# MAX77857.net
KiCad netlist of a schematic drawn in Altium Designer
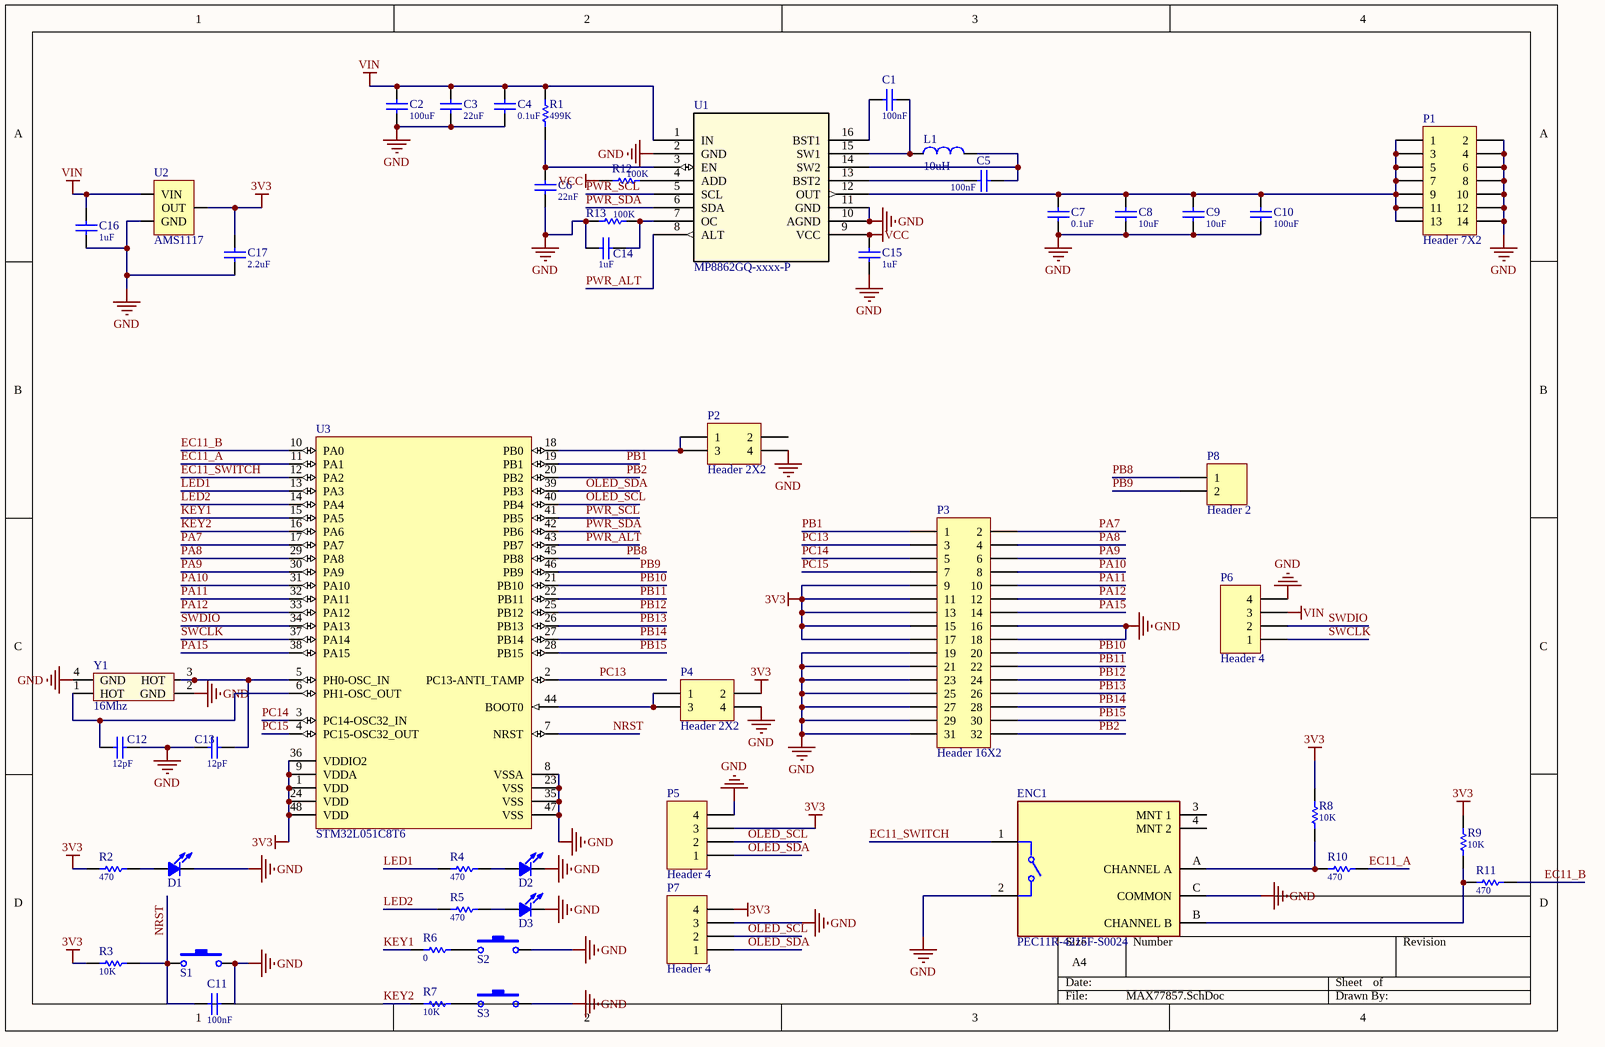
[diagram p0: MAX77857.SchDoc]

(export (version "E")
  (design (tool "Eeschema 10.0.6"))
  (components
    (comp (ref "C1")
      (value "100nF")
      (footprint "C0603-L")
      (description "贴片瓷片电容")
      (fields (field (name "Comment") "Cap-S"))
      (libsource (lib "CommonUsed") (part "Cap-S"))
    )
    (comp (ref "C2")
      (value "100uF")
      (footprint "C1206-L")
      (description "贴片瓷片电容")
      (fields (field (name "Comment") "Cap-S"))
      (libsource (lib "CommonUsed") (part "Cap-S"))
    )
    (comp (ref "C3")
      (value "22uF")
      (footprint "C0603-L")
      (description "贴片瓷片电容")
      (fields (field (name "Comment") "Cap-S"))
      (libsource (lib "CommonUsed") (part "Cap-S"))
    )
    (comp (ref "C4")
      (value "0.1uF")
      (footprint "C0603-L")
      (description "贴片瓷片电容")
      (fields (field (name "Comment") "Cap-S"))
      (libsource (lib "CommonUsed") (part "Cap-S"))
    )
    (comp (ref "C5")
      (value "100nF")
      (footprint "C0603-L")
      (description "贴片瓷片电容")
      (fields (field (name "Comment") "Cap-S"))
      (libsource (lib "CommonUsed") (part "Cap-S"))
    )
    (comp (ref "C6")
      (value "22nF")
      (footprint "C0603-L")
      (description "贴片瓷片电容")
      (fields (field (name "Comment") "Cap-S"))
      (libsource (lib "CommonUsed") (part "Cap-S"))
    )
    (comp (ref "C7")
      (value "0.1uF")
      (footprint "C0603-L")
      (description "贴片瓷片电容")
      (fields (field (name "Comment") "Cap-S"))
      (libsource (lib "CommonUsed") (part "Cap-S"))
    )
    (comp (ref "C8")
      (value "10uF")
      (footprint "C1206-L")
      (description "贴片瓷片电容")
      (fields (field (name "Comment") "Cap-S"))
      (libsource (lib "CommonUsed") (part "Cap-S"))
    )
    (comp (ref "C9")
      (value "10uF")
      (footprint "C1206-L")
      (description "贴片瓷片电容")
      (fields (field (name "Comment") "Cap-S"))
      (libsource (lib "CommonUsed") (part "Cap-S"))
    )
    (comp (ref "C10")
      (value "100uF")
      (footprint "C1206-L")
      (description "贴片瓷片电容")
      (fields (field (name "Comment") "Cap-S"))
      (libsource (lib "CommonUsed") (part "Cap-S"))
    )
    (comp (ref "C11")
      (value "100nF")
      (footprint "C0603-L")
      (description "贴片瓷片电容")
      (fields (field (name "Comment") "Cap-S"))
      (libsource (lib "CommonUsed") (part "Cap-S"))
    )
    (comp (ref "C12")
      (value "12pF")
      (footprint "C0603-L")
      (description "贴片瓷片电容")
      (fields (field (name "Comment") "Cap-S"))
      (libsource (lib "CommonUsed") (part "Cap-S"))
    )
    (comp (ref "C13")
      (value "12pF")
      (footprint "C0603-L")
      (description "贴片瓷片电容")
      (fields (field (name "Comment") "Cap-S"))
      (libsource (lib "CommonUsed") (part "Cap-S"))
    )
    (comp (ref "C14")
      (value "1uF")
      (footprint "C0603-L")
      (description "贴片瓷片电容")
      (fields (field (name "Comment") "Cap-S"))
      (libsource (lib "CommonUsed") (part "Cap-S"))
    )
    (comp (ref "C15")
      (value "1uF")
      (footprint "C0603-L")
      (description "贴片瓷片电容")
      (fields (field (name "Comment") "Cap-S"))
      (libsource (lib "CommonUsed") (part "Cap-S"))
    )
    (comp (ref "C16")
      (value "1uF")
      (footprint "C1206-L")
      (description "贴片瓷片电容")
      (fields (field (name "Comment") "Cap-S"))
      (libsource (lib "CommonUsed") (part "Cap-S"))
    )
    (comp (ref "C17")
      (value "2.2uF")
      (footprint "C0603-L")
      (description "贴片瓷片电容")
      (fields (field (name "Comment") "Cap-S"))
      (libsource (lib "CommonUsed") (part "Cap-S"))
    )
    (comp (ref "D1")
      (value "LED")
      (footprint "Led-0805_L")
      (description "发光二极管")
      (libsource (lib "CommonUsed") (part "LED"))
    )
    (comp (ref "D2")
      (value "LED")
      (footprint "Led-0805_L")
      (description "发光二极管")
      (libsource (lib "CommonUsed") (part "LED"))
    )
    (comp (ref "D3")
      (value "LED")
      (footprint "Led-0805_L")
      (description "发光二极管")
      (libsource (lib "CommonUsed") (part "LED"))
    )
    (comp (ref "ENC1")
      (value "PEC11R-4215F-S0024")
      (footprint "FP-PEC11R-4215F-S0024-MFG")
      (description "ROTARY ENCODER MECHANICAL 24PPR")
      (libsource (lib "Altium Content Vault") (part "5f1dd25a4c49fa66e7eeb899730fe11"))
    )
    (comp (ref "L1") (value "10uH") (footprint "L-6.5mm") (libsource (lib "CommonUsed") (part "Inductor")))
    (comp (ref "P1")
      (value "Header 7X2")
      (footprint "HDR2X7")
      (description "Header, 7-Pin, Dual row")
      (fields (field (name "PUBLISHER") "Altium Limited"))
      (libsource (lib "Miscellaneous Connectors") (part "Header 7X2"))
    )
    (comp (ref "P2")
      (value "Header 2X2")
      (footprint "HDR2X2")
      (description "Header, 2-Pin, Dual row")
      (fields (field (name "PUBLISHER") "Altium Limited"))
      (libsource (lib "Miscellaneous Connectors") (part "Header 2X2"))
    )
    (comp (ref "P3")
      (value "Header 16X2")
      (footprint "HDR2X16")
      (description "Header, 16-Pin, Dual row")
      (fields (field (name "PUBLISHER") "Altium Limited"))
      (libsource (lib "Miscellaneous Connectors") (part "Header 16X2"))
    )
    (comp (ref "P4")
      (value "Header 2X2")
      (footprint "HDR2X2")
      (description "Header, 2-Pin, Dual row")
      (fields (field (name "PUBLISHER") "Altium Limited"))
      (libsource (lib "Miscellaneous Connectors") (part "Header 2X2"))
    )
    (comp (ref "P5")
      (value "Header 4")
      (footprint "HDR1X4")
      (description "Header, 4-Pin")
      (fields (field (name "PUBLISHER") "Altium Limited"))
      (libsource (lib "Miscellaneous Connectors") (part "Header 4"))
    )
    (comp (ref "P6")
      (value "Header 4")
      (footprint "HDR1X4")
      (description "Header, 4-Pin")
      (fields (field (name "PUBLISHER") "Altium Limited"))
      (libsource (lib "Miscellaneous Connectors") (part "Header 4"))
    )
    (comp (ref "P7")
      (value "Header 4")
      (footprint "HDR1X4")
      (description "Header, 4-Pin")
      (fields (field (name "PUBLISHER") "Altium Limited"))
      (libsource (lib "Miscellaneous Connectors") (part "Header 4"))
    )
    (comp (ref "P8")
      (value "Header 2")
      (footprint "HDR1X2")
      (description "Header, 2-Pin")
      (fields (field (name "PUBLISHER") "Altium Limited"))
      (libsource (lib "Miscellaneous Connectors") (part "Header 2"))
    )
    (comp (ref "R1")
      (value "499K")
      (footprint "R0603-L")
      (description "贴片电阻")
      (fields (field (name "Comment") "R"))
      (libsource (lib "CommonUsed") (part "Res"))
    )
    (comp (ref "R2")
      (value "470")
      (footprint "R0603-L")
      (description "贴片电阻")
      (fields (field (name "Comment") "R"))
      (libsource (lib "CommonUsed") (part "Res"))
    )
    (comp (ref "R3")
      (value "10K")
      (footprint "R0603-L")
      (description "贴片电阻")
      (fields (field (name "Comment") "R"))
      (libsource (lib "CommonUsed") (part "Res"))
    )
    (comp (ref "R4")
      (value "470")
      (footprint "R0603-L")
      (description "贴片电阻")
      (fields (field (name "Comment") "R"))
      (libsource (lib "CommonUsed") (part "Res"))
    )
    (comp (ref "R5")
      (value "470")
      (footprint "R0603-L")
      (description "贴片电阻")
      (fields (field (name "Comment") "R"))
      (libsource (lib "CommonUsed") (part "Res"))
    )
    (comp (ref "R6")
      (value "0")
      (footprint "R0603-L")
      (description "贴片电阻")
      (fields (field (name "Comment") "R"))
      (libsource (lib "CommonUsed") (part "Res"))
    )
    (comp (ref "R7")
      (value "10K")
      (footprint "R0603-L")
      (description "贴片电阻")
      (fields (field (name "Comment") "R"))
      (libsource (lib "CommonUsed") (part "Res"))
    )
    (comp (ref "R8")
      (value "10K")
      (footprint "R0603-L")
      (description "贴片电阻")
      (fields (field (name "Comment") "R"))
      (libsource (lib "CommonUsed") (part "Res"))
    )
    (comp (ref "R9")
      (value "10K")
      (footprint "R0603-L")
      (description "贴片电阻")
      (fields (field (name "Comment") "R"))
      (libsource (lib "CommonUsed") (part "Res"))
    )
    (comp (ref "R10")
      (value "470")
      (footprint "R0603-L")
      (description "贴片电阻")
      (fields (field (name "Comment") "R"))
      (libsource (lib "CommonUsed") (part "Res"))
    )
    (comp (ref "R11")
      (value "470")
      (footprint "R0603-L")
      (description "贴片电阻")
      (fields (field (name "Comment") "R"))
      (libsource (lib "CommonUsed") (part "Res"))
    )
    (comp (ref "R12")
      (value "100K")
      (footprint "R0603-L")
      (description "贴片电阻")
      (fields (field (name "Comment") "R"))
      (libsource (lib "CommonUsed") (part "Res"))
    )
    (comp (ref "R13")
      (value "100K")
      (footprint "R0603-L")
      (description "贴片电阻")
      (fields (field (name "Comment") "R"))
      (libsource (lib "CommonUsed") (part "Res"))
    )
    (comp (ref "S1")
      (value "SW-PB2")
      (footprint "SW-PB2-SMD")
      (description "贴片式2脚微动开关")
      (libsource (lib "CommonUsed") (part "SW-PB2"))
    )
    (comp (ref "S2")
      (value "SW-PB2")
      (footprint "SW-PB2-SMD")
      (description "贴片式2脚微动开关")
      (libsource (lib "CommonUsed") (part "SW-PB2"))
    )
    (comp (ref "S3")
      (value "SW-PB2")
      (footprint "SW-PB2-SMD")
      (description "贴片式2脚微动开关")
      (libsource (lib "CommonUsed") (part "SW-PB2"))
    )
    (comp (ref "U1")
      (value "MP8862GQ-xxxx-P")
      (footprint "QFN-3x3_MP8862_MNP")
      (description "No Description Available")
      (libsource (lib "MP8862GQ-xxxx-P") (part "MP8862GQ-xxxx-P"))
    )
    (comp (ref "U2") (value "AMS1117") (footprint "SOT-223") (libsource (lib "CommonUsed") (part "AMS1117")))
    (comp (ref "U3")
      (value "STM32L051C8T6")
      (footprint "STM-LQFP48_L")
      (libsource (lib "Altium Content Vault") (part "STM-STM32L051-LQFP-48"))
    )
    (comp (ref "Y1")
      (value "16Mhz")
      (footprint "XTAL3225")
      (description "3225贴片无源晶振")
      (libsource (lib "STM32H743核心板封装库") (part "XTAL_3225"))
    )
  )
  (nets
    (net (code "1") (name "/EC11_A") (class "Default")
      (node (ref "R10") (pin "2") (pinfunction "2_2") (pintype "passive"))
      (node (ref "U3") (pin "11") (pinfunction "PA1_11") (pintype "bidirectional"))
    )
    (net (code "2") (name "/EC11_B") (class "Default")
      (node (ref "R11") (pin "2") (pinfunction "2_2") (pintype "passive"))
      (node (ref "U3") (pin "10") (pinfunction "PA0_10") (pintype "bidirectional"))
    )
    (net (code "3") (name "/EC11_SWITCH") (class "Default")
      (node (ref "ENC1") (pin "1") (pinfunction "1_1") (pintype "passive"))
      (node (ref "U3") (pin "12") (pinfunction "PA2_12") (pintype "bidirectional"))
    )
    (net (code "4") (name "/KEY1") (class "Default")
      (node (ref "R6") (pin "2") (pinfunction "2_2") (pintype "passive"))
      (node (ref "U3") (pin "15") (pinfunction "PA5_15") (pintype "bidirectional"))
    )
    (net (code "5") (name "/KEY2") (class "Default")
      (node (ref "R7") (pin "2") (pinfunction "2_2") (pintype "passive"))
      (node (ref "U3") (pin "16") (pinfunction "PA6_16") (pintype "bidirectional"))
    )
    (net (code "6") (name "/LED1") (class "Default")
      (node (ref "R4") (pin "2") (pinfunction "2_2") (pintype "passive"))
      (node (ref "U3") (pin "13") (pinfunction "PA3_13") (pintype "bidirectional"))
    )
    (net (code "7") (name "/LED2") (class "Default")
      (node (ref "R5") (pin "2") (pinfunction "2_2") (pintype "passive"))
      (node (ref "U3") (pin "14") (pinfunction "PA4_14") (pintype "bidirectional"))
    )
    (net (code "8") (name "/NRST") (class "Default")
      (node (ref "C11") (pin "1") (pinfunction "1_1") (pintype "passive"))
      (node (ref "R3") (pin "1") (pinfunction "1_1") (pintype "passive"))
      (node (ref "S1") (pin "1") (pinfunction "1_1") (pintype "passive"))
      (node (ref "U3") (pin "7") (pinfunction "NRST_7") (pintype "bidirectional"))
    )
    (net (code "9") (name "/OLED_SCL") (class "Default")
      (node (ref "P5") (pin "2") (pinfunction "2_2") (pintype "passive"))
      (node (ref "P7") (pin "2") (pinfunction "2_2") (pintype "passive"))
      (node (ref "U3") (pin "40") (pinfunction "PB4_40") (pintype "bidirectional"))
    )
    (net (code "10") (name "/OLED_SDA") (class "Default")
      (node (ref "P5") (pin "1") (pinfunction "1_1") (pintype "passive"))
      (node (ref "P7") (pin "1") (pinfunction "1_1") (pintype "passive"))
      (node (ref "U3") (pin "39") (pinfunction "PB3_39") (pintype "bidirectional"))
    )
    (net (code "11") (name "/PA7") (class "Default")
      (node (ref "P3") (pin "2") (pinfunction "2_2") (pintype "passive"))
      (node (ref "U3") (pin "17") (pinfunction "PA7_17") (pintype "bidirectional"))
    )
    (net (code "12") (name "/PA8") (class "Default")
      (node (ref "P3") (pin "4") (pinfunction "4_4") (pintype "passive"))
      (node (ref "U3") (pin "29") (pinfunction "PA8_29") (pintype "bidirectional"))
    )
    (net (code "13") (name "/PA9") (class "Default")
      (node (ref "P3") (pin "6") (pinfunction "6_6") (pintype "passive"))
      (node (ref "U3") (pin "30") (pinfunction "PA9_30") (pintype "bidirectional"))
    )
    (net (code "14") (name "/PA10") (class "Default")
      (node (ref "P3") (pin "8") (pinfunction "8_8") (pintype "passive"))
      (node (ref "U3") (pin "31") (pinfunction "PA10_31") (pintype "bidirectional"))
    )
    (net (code "15") (name "/PA11") (class "Default")
      (node (ref "P3") (pin "10") (pinfunction "10_10") (pintype "passive"))
      (node (ref "U3") (pin "32") (pinfunction "PA11_32") (pintype "bidirectional"))
    )
    (net (code "16") (name "/PA12") (class "Default")
      (node (ref "P3") (pin "12") (pinfunction "12_12") (pintype "passive"))
      (node (ref "U3") (pin "33") (pinfunction "PA12_33") (pintype "bidirectional"))
    )
    (net (code "17") (name "/PA15") (class "Default")
      (node (ref "P3") (pin "14") (pinfunction "14_14") (pintype "passive"))
      (node (ref "U3") (pin "38") (pinfunction "PA15_38") (pintype "bidirectional"))
    )
    (net (code "18") (name "/PB1") (class "Default")
      (node (ref "P3") (pin "1") (pinfunction "1_1") (pintype "passive"))
      (node (ref "U3") (pin "19") (pinfunction "PB1_19") (pintype "bidirectional"))
    )
    (net (code "19") (name "/PB2") (class "Default")
      (node (ref "P3") (pin "32") (pinfunction "32_32") (pintype "passive"))
      (node (ref "U3") (pin "20") (pinfunction "PB2_20") (pintype "bidirectional"))
    )
    (net (code "20") (name "/PB8") (class "Default")
      (node (ref "P8") (pin "1") (pinfunction "1_1") (pintype "passive"))
      (node (ref "U3") (pin "45") (pinfunction "PB8_45") (pintype "bidirectional"))
    )
    (net (code "21") (name "/PB9") (class "Default")
      (node (ref "P8") (pin "2") (pinfunction "2_2") (pintype "passive"))
      (node (ref "U3") (pin "46") (pinfunction "PB9_46") (pintype "bidirectional"))
    )
    (net (code "22") (name "/PB10") (class "Default")
      (node (ref "P3") (pin "20") (pinfunction "20_20") (pintype "passive"))
      (node (ref "U3") (pin "21") (pinfunction "PB10_21") (pintype "bidirectional"))
    )
    (net (code "23") (name "/PB11") (class "Default")
      (node (ref "P3") (pin "22") (pinfunction "22_22") (pintype "passive"))
      (node (ref "U3") (pin "22") (pinfunction "PB11_22") (pintype "bidirectional"))
    )
    (net (code "24") (name "/PB12") (class "Default")
      (node (ref "P3") (pin "24") (pinfunction "24_24") (pintype "passive"))
      (node (ref "U3") (pin "25") (pinfunction "PB12_25") (pintype "bidirectional"))
    )
    (net (code "25") (name "/PB13") (class "Default")
      (node (ref "P3") (pin "26") (pinfunction "26_26") (pintype "passive"))
      (node (ref "U3") (pin "26") (pinfunction "PB13_26") (pintype "bidirectional"))
    )
    (net (code "26") (name "/PB14") (class "Default")
      (node (ref "P3") (pin "28") (pinfunction "28_28") (pintype "passive"))
      (node (ref "U3") (pin "27") (pinfunction "PB14_27") (pintype "bidirectional"))
    )
    (net (code "27") (name "/PB15") (class "Default")
      (node (ref "P3") (pin "30") (pinfunction "30_30") (pintype "passive"))
      (node (ref "U3") (pin "28") (pinfunction "PB15_28") (pintype "bidirectional"))
    )
    (net (code "28") (name "/PC13") (class "Default")
      (node (ref "P3") (pin "3") (pinfunction "3_3") (pintype "passive"))
      (node (ref "U3") (pin "2") (pinfunction "PC13-ANTI_TAMP_2") (pintype "bidirectional"))
    )
    (net (code "29") (name "/PC14") (class "Default")
      (node (ref "P3") (pin "5") (pinfunction "5_5") (pintype "passive"))
      (node (ref "U3") (pin "3") (pinfunction "PC14-OSC32_IN_3") (pintype "bidirectional"))
    )
    (net (code "30") (name "/PC15") (class "Default")
      (node (ref "P3") (pin "7") (pinfunction "7_7") (pintype "passive"))
      (node (ref "U3") (pin "4") (pinfunction "PC15-OSC32_OUT_4") (pintype "bidirectional"))
    )
    (net (code "31") (name "/PWR_ALT") (class "Default")
      (node (ref "U1") (pin "8") (pinfunction "ALT_8") (pintype "output"))
      (node (ref "U3") (pin "43") (pinfunction "PB7_43") (pintype "bidirectional"))
    )
    (net (code "32") (name "/PWR_SCL") (class "Default")
      (node (ref "U1") (pin "5") (pinfunction "SCL_5") (pintype "passive"))
      (node (ref "U3") (pin "41") (pinfunction "PB5_41") (pintype "bidirectional"))
    )
    (net (code "33") (name "/PWR_SDA") (class "Default")
      (node (ref "U1") (pin "6") (pinfunction "SDA_6") (pintype "passive"))
      (node (ref "U3") (pin "42") (pinfunction "PB6_42") (pintype "bidirectional"))
    )
    (net (code "34") (name "/SWCLK") (class "Default")
      (node (ref "P6") (pin "1") (pinfunction "1_1") (pintype "passive"))
      (node (ref "U3") (pin "37") (pinfunction "PA14_37") (pintype "bidirectional"))
    )
    (net (code "35") (name "/SWDIO") (class "Default")
      (node (ref "P6") (pin "2") (pinfunction "2_2") (pintype "passive"))
      (node (ref "U3") (pin "34") (pinfunction "PA13_34") (pintype "bidirectional"))
    )
    (net (code "36") (name "3V3") (class "Default")
      (node (ref "C17") (pin "2") (pinfunction "2_2") (pintype "passive"))
      (node (ref "P3") (pin "11") (pinfunction "11_11") (pintype "passive"))
      (node (ref "P3") (pin "13") (pinfunction "13_13") (pintype "passive"))
      (node (ref "P3") (pin "15") (pinfunction "15_15") (pintype "passive"))
      (node (ref "P3") (pin "17") (pinfunction "17_17") (pintype "passive"))
      (node (ref "P3") (pin "9") (pinfunction "9_9") (pintype "passive"))
      (node (ref "P4") (pin "2") (pinfunction "2_2") (pintype "passive"))
      (node (ref "P5") (pin "3") (pinfunction "3_3") (pintype "passive"))
      (node (ref "P7") (pin "4") (pinfunction "4_4") (pintype "passive"))
      (node (ref "R2") (pin "2") (pinfunction "2_2") (pintype "passive"))
      (node (ref "R3") (pin "2") (pinfunction "2_2") (pintype "passive"))
      (node (ref "R8") (pin "2") (pinfunction "2_2") (pintype "passive"))
      (node (ref "R9") (pin "2") (pinfunction "2_2") (pintype "passive"))
      (node (ref "U2") (pin "2") (pinfunction "OUT_2") (pintype "passive"))
      (node (ref "U3") (pin "1") (pinfunction "VDD_1") (pintype "power_in"))
      (node (ref "U3") (pin "24") (pinfunction "VDD_24") (pintype "power_in"))
      (node (ref "U3") (pin "36") (pinfunction "VDDIO2_36") (pintype "power_in"))
      (node (ref "U3") (pin "48") (pinfunction "VDD_48") (pintype "power_in"))
      (node (ref "U3") (pin "9") (pinfunction "VDDA_9") (pintype "power_in"))
    )
    (net (code "37") (name "GND") (class "Default")
      (node (ref "C10") (pin "1") (pinfunction "1_1") (pintype "passive"))
      (node (ref "C11") (pin "2") (pinfunction "2_2") (pintype "passive"))
      (node (ref "C12") (pin "1") (pinfunction "1_1") (pintype "passive"))
      (node (ref "C13") (pin "2") (pinfunction "2_2") (pintype "passive"))
      (node (ref "C14") (pin "1") (pinfunction "1_1") (pintype "passive"))
      (node (ref "C15") (pin "2") (pinfunction "2_2") (pintype "passive"))
      (node (ref "C16") (pin "1") (pinfunction "1_1") (pintype "passive"))
      (node (ref "C17") (pin "1") (pinfunction "1_1") (pintype "passive"))
      (node (ref "C2") (pin "1") (pinfunction "1_1") (pintype "passive"))
      (node (ref "C3") (pin "1") (pinfunction "1_1") (pintype "passive"))
      (node (ref "C4") (pin "2") (pinfunction "2_2") (pintype "passive"))
      (node (ref "C6") (pin "2") (pinfunction "2_2") (pintype "passive"))
      (node (ref "C7") (pin "1") (pinfunction "1_1") (pintype "passive"))
      (node (ref "C8") (pin "1") (pinfunction "1_1") (pintype "passive"))
      (node (ref "C9") (pin "1") (pinfunction "1_1") (pintype "passive"))
      (node (ref "D1") (pin "2") (pinfunction "2_2") (pintype "passive"))
      (node (ref "D2") (pin "2") (pinfunction "2_2") (pintype "passive"))
      (node (ref "D3") (pin "2") (pinfunction "2_2") (pintype "passive"))
      (node (ref "ENC1") (pin "2") (pinfunction "2_2") (pintype "passive"))
      (node (ref "ENC1") (pin "C") (pinfunction "COMMON_C") (pintype "passive"))
      (node (ref "P1") (pin "10") (pinfunction "10_10") (pintype "passive"))
      (node (ref "P1") (pin "12") (pinfunction "12_12") (pintype "passive"))
      (node (ref "P1") (pin "14") (pinfunction "14_14") (pintype "passive"))
      (node (ref "P1") (pin "2") (pinfunction "2_2") (pintype "passive"))
      (node (ref "P1") (pin "4") (pinfunction "4_4") (pintype "passive"))
      (node (ref "P1") (pin "6") (pinfunction "6_6") (pintype "passive"))
      (node (ref "P1") (pin "8") (pinfunction "8_8") (pintype "passive"))
      (node (ref "P2") (pin "4") (pinfunction "4_4") (pintype "passive"))
      (node (ref "P3") (pin "16") (pinfunction "16_16") (pintype "passive"))
      (node (ref "P3") (pin "18") (pinfunction "18_18") (pintype "passive"))
      (node (ref "P3") (pin "19") (pinfunction "19_19") (pintype "passive"))
      (node (ref "P3") (pin "21") (pinfunction "21_21") (pintype "passive"))
      (node (ref "P3") (pin "23") (pinfunction "23_23") (pintype "passive"))
      (node (ref "P3") (pin "25") (pinfunction "25_25") (pintype "passive"))
      (node (ref "P3") (pin "27") (pinfunction "27_27") (pintype "passive"))
      (node (ref "P3") (pin "29") (pinfunction "29_29") (pintype "passive"))
      (node (ref "P3") (pin "31") (pinfunction "31_31") (pintype "passive"))
      (node (ref "P4") (pin "4") (pinfunction "4_4") (pintype "passive"))
      (node (ref "P5") (pin "4") (pinfunction "4_4") (pintype "passive"))
      (node (ref "P6") (pin "4") (pinfunction "4_4") (pintype "passive"))
      (node (ref "P7") (pin "3") (pinfunction "3_3") (pintype "passive"))
      (node (ref "R13") (pin "2") (pinfunction "2_2") (pintype "passive"))
      (node (ref "S1") (pin "2") (pinfunction "2_2") (pintype "passive"))
      (node (ref "S2") (pin "2") (pinfunction "2_2") (pintype "passive"))
      (node (ref "S3") (pin "2") (pinfunction "2_2") (pintype "passive"))
      (node (ref "U1") (pin "10") (pinfunction "AGND_10") (pintype "power_in"))
      (node (ref "U1") (pin "11") (pinfunction "GND_11") (pintype "power_in"))
      (node (ref "U1") (pin "2") (pinfunction "GND_2") (pintype "power_in"))
      (node (ref "U2") (pin "1") (pinfunction "GND_1") (pintype "passive"))
      (node (ref "U3") (pin "23") (pinfunction "VSS_23") (pintype "power_in"))
      (node (ref "U3") (pin "35") (pinfunction "VSS_35") (pintype "power_in"))
      (node (ref "U3") (pin "47") (pinfunction "VSS_47") (pintype "power_in"))
      (node (ref "U3") (pin "8") (pinfunction "VSSA_8") (pintype "power_in"))
      (node (ref "Y1") (pin "2") (pinfunction "GND_2") (pintype "passive"))
      (node (ref "Y1") (pin "4") (pinfunction "GND_4") (pintype "passive"))
    )
    (net (code "38") (name "Net-(D1-Pad1)") (class "Default")
      (node (ref "D1") (pin "1") (pinfunction "1_1") (pintype "passive"))
      (node (ref "R2") (pin "1") (pinfunction "1_1") (pintype "passive"))
    )
    (net (code "39") (name "Net-(D2-Pad1)") (class "Default")
      (node (ref "D2") (pin "1") (pinfunction "1_1") (pintype "passive"))
      (node (ref "R4") (pin "1") (pinfunction "1_1") (pintype "passive"))
    )
    (net (code "40") (name "Net-(D3-Pad1)") (class "Default")
      (node (ref "D3") (pin "1") (pinfunction "1_1") (pintype "passive"))
      (node (ref "R5") (pin "1") (pinfunction "1_1") (pintype "passive"))
    )
    (net (code "41") (name "Net-(ENC1-CHANNEL_A)") (class "Default")
      (node (ref "ENC1") (pin "A") (pinfunction "CHANNEL_A_A") (pintype "passive"))
      (node (ref "R10") (pin "1") (pinfunction "1_1") (pintype "passive"))
      (node (ref "R8") (pin "1") (pinfunction "1_1") (pintype "passive"))
    )
    (net (code "42") (name "Net-(ENC1-CHANNEL_B)") (class "Default")
      (node (ref "ENC1") (pin "B") (pinfunction "CHANNEL_B_B") (pintype "passive"))
      (node (ref "R11") (pin "1") (pinfunction "1_1") (pintype "passive"))
      (node (ref "R9") (pin "1") (pinfunction "1_1") (pintype "passive"))
    )
    (net (code "43") (name "Net-(R6-Pad1)") (class "Default")
      (node (ref "R6") (pin "1") (pinfunction "1_1") (pintype "passive"))
      (node (ref "S2") (pin "1") (pinfunction "1_1") (pintype "passive"))
    )
    (net (code "44") (name "Net-(R7-Pad1)") (class "Default")
      (node (ref "R7") (pin "1") (pinfunction "1_1") (pintype "passive"))
      (node (ref "S3") (pin "1") (pinfunction "1_1") (pintype "passive"))
    )
    (net (code "45") (name "Net-(U1-ADD)") (class "Default")
      (node (ref "R12") (pin "1") (pinfunction "1_1") (pintype "passive"))
      (node (ref "U1") (pin "4") (pinfunction "ADD_4") (pintype "passive"))
    )
    (net (code "46") (name "Net-(U1-BST1)") (class "Default")
      (node (ref "C1") (pin "1") (pinfunction "1_1") (pintype "passive"))
      (node (ref "U1") (pin "16") (pinfunction "BST1_16") (pintype "passive"))
    )
    (net (code "47") (name "Net-(U1-BST2)") (class "Default")
      (node (ref "C5") (pin "1") (pinfunction "1_1") (pintype "passive"))
      (node (ref "U1") (pin "13") (pinfunction "BST2_13") (pintype "passive"))
    )
    (net (code "48") (name "Net-(U1-EN)") (class "Default")
      (node (ref "C6") (pin "1") (pinfunction "1_1") (pintype "passive"))
      (node (ref "R1") (pin "1") (pinfunction "1_1") (pintype "passive"))
      (node (ref "U1") (pin "3") (pinfunction "EN_3") (pintype "bidirectional"))
    )
    (net (code "49") (name "Net-(U1-OC)") (class "Default")
      (node (ref "C14") (pin "2") (pinfunction "2_2") (pintype "passive"))
      (node (ref "R13") (pin "1") (pinfunction "1_1") (pintype "passive"))
      (node (ref "U1") (pin "7") (pinfunction "OC_7") (pintype "passive"))
    )
    (net (code "50") (name "Net-(U1-OUT)") (class "Default")
      (node (ref "C10") (pin "2") (pinfunction "2_2") (pintype "passive"))
      (node (ref "C7") (pin "2") (pinfunction "2_2") (pintype "passive"))
      (node (ref "C8") (pin "2") (pinfunction "2_2") (pintype "passive"))
      (node (ref "C9") (pin "2") (pinfunction "2_2") (pintype "passive"))
      (node (ref "P1") (pin "1") (pinfunction "1_1") (pintype "passive"))
      (node (ref "P1") (pin "11") (pinfunction "11_11") (pintype "passive"))
      (node (ref "P1") (pin "13") (pinfunction "13_13") (pintype "passive"))
      (node (ref "P1") (pin "3") (pinfunction "3_3") (pintype "passive"))
      (node (ref "P1") (pin "5") (pinfunction "5_5") (pintype "passive"))
      (node (ref "P1") (pin "7") (pinfunction "7_7") (pintype "passive"))
      (node (ref "P1") (pin "9") (pinfunction "9_9") (pintype "passive"))
      (node (ref "U1") (pin "12") (pinfunction "OUT_12") (pintype "output"))
    )
    (net (code "51") (name "Net-(U1-SW1)") (class "Default")
      (node (ref "C1") (pin "2") (pinfunction "2_2") (pintype "passive"))
      (node (ref "L1") (pin "1") (pinfunction "1_1") (pintype "passive"))
      (node (ref "U1") (pin "15") (pinfunction "SW1_15") (pintype "passive"))
    )
    (net (code "52") (name "Net-(U1-SW2)") (class "Default")
      (node (ref "C5") (pin "2") (pinfunction "2_2") (pintype "passive"))
      (node (ref "L1") (pin "2") (pinfunction "2_2") (pintype "passive"))
      (node (ref "U1") (pin "14") (pinfunction "SW2_14") (pintype "passive"))
    )
    (net (code "53") (name "Net-(U3-BOOT0)") (class "Default")
      (node (ref "P4") (pin "1") (pinfunction "1_1") (pintype "passive"))
      (node (ref "P4") (pin "3") (pinfunction "3_3") (pintype "passive"))
      (node (ref "U3") (pin "44") (pinfunction "BOOT0_44") (pintype "input"))
    )
    (net (code "54") (name "Net-(U3-PB0)") (class "Default")
      (node (ref "P2") (pin "1") (pinfunction "1_1") (pintype "passive"))
      (node (ref "P2") (pin "3") (pinfunction "3_3") (pintype "passive"))
      (node (ref "U3") (pin "18") (pinfunction "PB0_18") (pintype "bidirectional"))
    )
    (net (code "55") (name "Net-(U3-PH0-OSC_IN)") (class "Default")
      (node (ref "C13") (pin "1") (pinfunction "1_1") (pintype "passive"))
      (node (ref "U3") (pin "5") (pinfunction "PH0-OSC_IN_5") (pintype "bidirectional"))
      (node (ref "Y1") (pin "3") (pinfunction "HOT_3") (pintype "passive"))
    )
    (net (code "56") (name "Net-(U3-PH1-OSC_OUT)") (class "Default")
      (node (ref "C12") (pin "2") (pinfunction "2_2") (pintype "passive"))
      (node (ref "U3") (pin "6") (pinfunction "PH1-OSC_OUT_6") (pintype "bidirectional"))
      (node (ref "Y1") (pin "1") (pinfunction "HOT_1") (pintype "passive"))
    )
    (net (code "57") (name "VCC") (class "Default")
      (node (ref "C15") (pin "1") (pinfunction "1_1") (pintype "passive"))
      (node (ref "R12") (pin "2") (pinfunction "2_2") (pintype "passive"))
      (node (ref "U1") (pin "9") (pinfunction "VCC_9") (pintype "power_in"))
    )
    (net (code "58") (name "VIN") (class "Default")
      (node (ref "C16") (pin "2") (pinfunction "2_2") (pintype "passive"))
      (node (ref "C2") (pin "2") (pinfunction "2_2") (pintype "passive"))
      (node (ref "C3") (pin "2") (pinfunction "2_2") (pintype "passive"))
      (node (ref "C4") (pin "1") (pinfunction "1_1") (pintype "passive"))
      (node (ref "P6") (pin "3") (pinfunction "3_3") (pintype "passive"))
      (node (ref "R1") (pin "2") (pinfunction "2_2") (pintype "passive"))
      (node (ref "U1") (pin "1") (pinfunction "IN_1") (pintype "power_in"))
      (node (ref "U2") (pin "3") (pinfunction "VIN_3") (pintype "passive"))
    )
    (net (code "59") (name "unconnected-(ENC1-MNT_1-Pad3)") (class "Default")
      (node (ref "ENC1") (pin "3") (pinfunction "MNT_1_3") (pintype "passive"))
    )
    (net (code "60") (name "unconnected-(ENC1-MNT_2-Pad4)") (class "Default")
      (node (ref "ENC1") (pin "4") (pinfunction "MNT_2_4") (pintype "passive"))
    )
    (net (code "61") (name "unconnected-(P2-Pad2)") (class "Default")
      (node (ref "P2") (pin "2") (pinfunction "2_2") (pintype "passive"))
    )
  )
)
